# PFC_control_board.net
KiCad netlist of a schematic drawn in Altium Designer
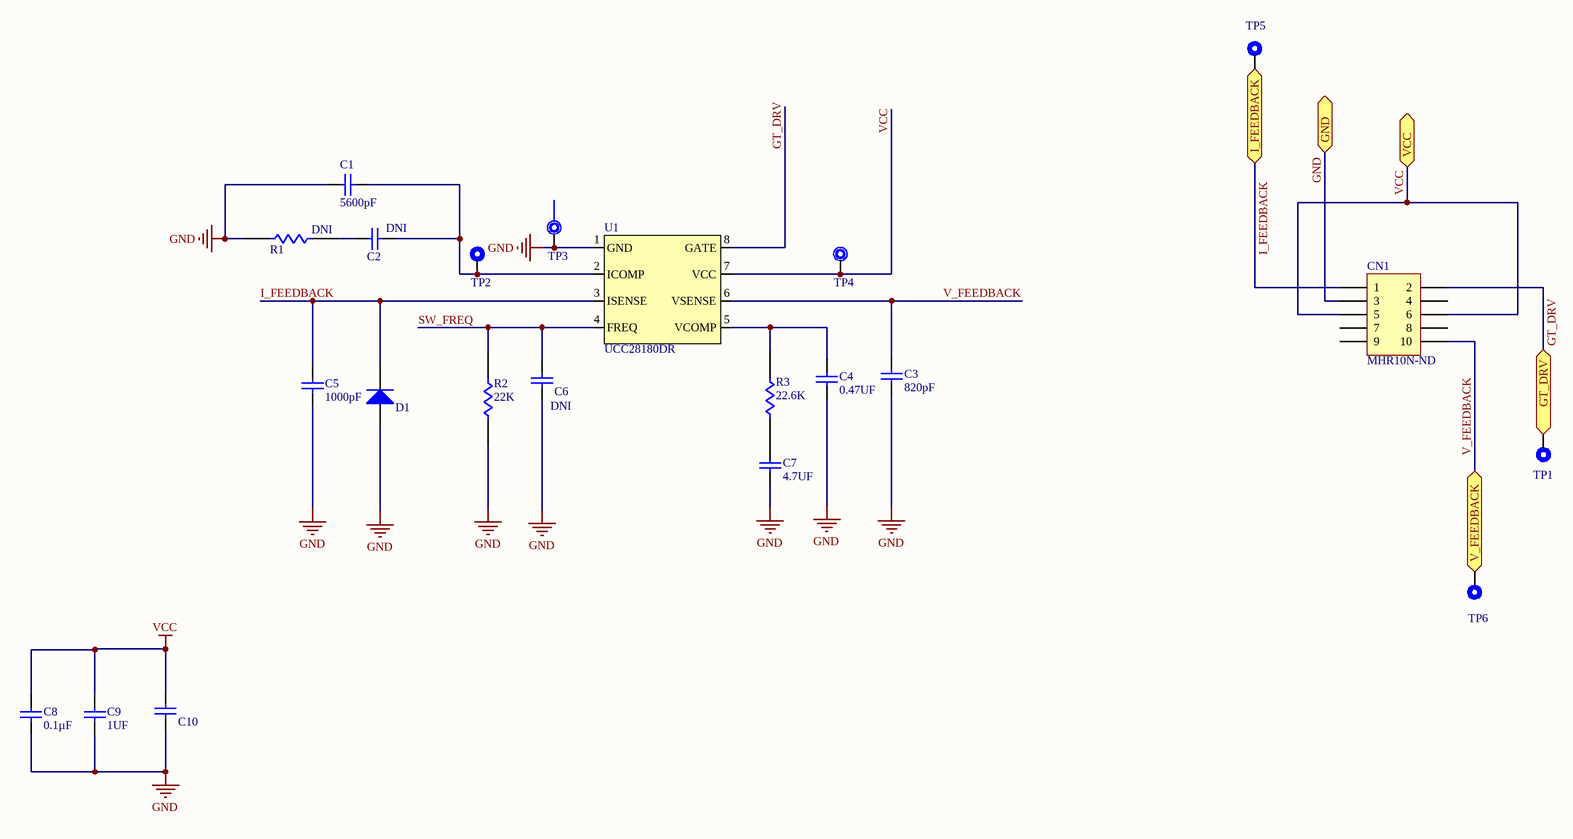
[diagram p0: PFC control board.SchDoc]

(export (version "E")
  (design (tool "Eeschema 10.0.6"))
  (components
    (comp (ref "C1")
      (value "GRM2195C1H562FA01D")
      (footprint "CAP0805_NEW")
      (description "CAP CER 5600PF 50V C0G/NP0 0805")
      (fields
        (field (name "MANUFACTURER") "Murata Electronics North America")
        (field (name "TOLERANCE") "±1%")
        (field (name "CAPACITANCE") "5600pF")
      )
      (libsource (lib "ucc28180-V04") (part "GRM2195C1H562FA01D"))
    )
    (comp (ref "C2")
      (value "C0805_Generic")
      (footprint "CAP0805_NEW")
      (libsource (lib "ucc28180-V04") (part "C0805_Generic"))
    )
    (comp (ref "C3")
      (value "CC0805KRX7R9BB821")
      (footprint "CAP0805_NEW")
      (description "CAP CER 820PF 50V X7R 0805")
      (fields
        (field (name "MANUFACTURER") "Yageo")
        (field (name "TOLERANCE") "±10%")
        (field (name "CAPACITANCE") "820pF")
      )
      (libsource (lib "ucc28180-V04") (part "CC0805KRX7R9BB821"))
    )
    (comp (ref "C4")
      (value "C0805C474J5RACTU")
      (footprint "CAP0805_NEW")
      (description "CAP CER 0.47UF 50V X7R 0805")
      (fields
        (field (name "MANUFACTURER") "KEMET")
        (field (name "TOLERANCE") "±5%")
        (field (name "CAPACITANCE") "0.47UF")
      )
      (libsource (lib "ucc28180-V04") (part "C0805C474J5RACTU"))
    )
    (comp (ref "C5")
      (value "C0805C102J5GACTU")
      (footprint "CAP0805_NEW")
      (description "CAP CER 1000PF 50V C0G/NP0 0805")
      (fields
        (field (name "MANUFACTURER") "KEMET")
        (field (name "TOLERANCE") "±5%")
        (field (name "CAPACITANCE") "1000pF")
      )
      (libsource (lib "ucc28180-V04") (part "C0805C102J5GACTU"))
    )
    (comp (ref "C6")
      (value "C0805_Generic")
      (footprint "CAP0805_NEW")
      (libsource (lib "ucc28180-V04") (part "C0805_Generic"))
    )
    (comp (ref "C7")
      (value "GRM21BR61H475KE51L")
      (footprint "CAP0805_NEW")
      (description "CAP CER 4.7UF 50V X5R 0805")
      (fields
        (field (name "MANUFACTURER") "Murata Electronics North America")
        (field (name "TOLERANCE") "±10%")
        (field (name "CAPACITANCE") "4.7UF")
      )
      (libsource (lib "ucc28180-V04") (part "GRM21BR61H475KE51L"))
    )
    (comp (ref "C8")
      (value "C0805C104J5RACAUTO")
      (footprint "CAP0805_NEW")
      (description "CAP CER 0.1UF 50V X7R 0805")
      (fields
        (field (name "MANUFACTURER") "KEMET")
        (field (name "TOLERANCE") "±5%")
        (field (name "CAPACITANCE") "0.1µF")
      )
      (libsource (lib "ucc28180-V04") (part "C0805C104J5RACAUTO"))
    )
    (comp (ref "C9")
      (value "CC0805JKX7R9BB105")
      (footprint "CAP0805_NEW")
      (description "CAP CER 1UF 50V X7R 0805")
      (fields
        (field (name "MANUFACTURER") "Yageo")
        (field (name "TOLERANCE") "±5%")
        (field (name "CAPACITANCE") "1UF")
      )
      (libsource (lib "ucc28180-V04") (part "CC0805JKX7R9BB105"))
    )
    (comp (ref "C10")
      (value "C0805_Generic")
      (footprint "CAP0805_NEW")
      (libsource (lib "ucc28180-V04") (part "C0805_Generic"))
    )
    (comp (ref "CN1")
      (value "MHR10N-ND")
      (footprint "3M15452")
      (description "CONN HEADER 10PS R/A LONG LATCH")
      (fields
        (field (name "MANUFACTURER") "3M")
        (field (name "MANUFACTURER PART NUMBER") "N3793-5302RB")
        (field (name "SUPPLIER PART NUMBER 1") "MHR10N-ND")
      )
      (libsource (lib "ucc28180-V03") (part "MHR10N-ND"))
    )
    (comp (ref "D1")
      (value "MRA4004T3G")
      (footprint "MRA4004T3G")
      (libsource (lib "ucc28180-V04") (part "MRA4004T3G"))
    )
    (comp (ref "R1")
      (value "R0805_Generic")
      (footprint "RES0805_New")
      (libsource (lib "ucc28180-V04") (part "R0805_Generic"))
    )
    (comp (ref "R2")
      (value "22K")
      (footprint "RES0805_New")
      (description "RES SMD 22K OHM 1% 1/8W 0805")
      (fields
        (field (name "MANUFACTURER") "Yageo")
        (field (name "MANUFACTURER PART NUMBER") "RC0805FR-0722KL")
      )
      (libsource (lib "ucc28180-V04") (part "RC0805FR-0722KL"))
    )
    (comp (ref "R3")
      (value "22.6K")
      (footprint "RES0805_New")
      (description "RES SMD 22.6K OHM 1% 1/8W 0805")
      (fields
        (field (name "MANUFACTURER") "Yageo")
        (field (name "MANUFACTURER PART NUMBER") "RC0805FR-0722K6L")
      )
      (libsource (lib "ucc28180-V04") (part "RC0805FR-0722K6L"))
    )
    (comp (ref "TP1")
      (value "5006")
      (footprint "Test Point")
      (description "TEST POINT PC COMPACT .063\"D BLK")
      (libsource (lib "ucc28180-V03") (part "5006"))
    )
    (comp (ref "TP2")
      (value "5006")
      (footprint "Test Point")
      (description "TEST POINT PC COMPACT .063\"D BLK")
      (libsource (lib "ucc28180-V03") (part "5006"))
    )
    (comp (ref "TP3")
      (value "TP-Slot")
      (footprint "TP-Slot")
      (libsource (lib "ucc28180-V03") (part "TP-Slot"))
    )
    (comp (ref "TP4") (value "TP-SM") (footprint "TP-SM") (libsource (lib "ucc28180-V03") (part "TP-SM")))
    (comp (ref "TP5")
      (value "5006")
      (footprint "Test Point")
      (description "TEST POINT PC COMPACT .063\"D BLK")
      (libsource (lib "ucc28180-V03") (part "5006"))
    )
    (comp (ref "TP6")
      (value "5006")
      (footprint "Test Point")
      (description "TEST POINT PC COMPACT .063\"D BLK")
      (libsource (lib "ucc28180-V03") (part "5006"))
    )
    (comp (ref "U1")
      (value "UCC28180DR")
      (footprint "SOP127P600X175-8N")
      (description "IC PFC CTRLR AVERAGE CURR 8SOIC")
      (libsource (lib "ucc28180-V03") (part "UCC28180DR"))
    )
  )
  (nets
    (net (code "1") (name "/GT_DRV") (class "Default")
      (node (ref "CN1") (pin "2") (pinfunction "2_2") (pintype "passive"))
      (node (ref "TP1") (pin "1") (pinfunction "1_1") (pintype "passive"))
      (node (ref "U1") (pin "8") (pinfunction "GATE_8") (pintype "passive"))
    )
    (net (code "2") (name "/I_FEEDBACK") (class "Default")
      (node (ref "C5") (pin "2") (pinfunction "2_2") (pintype "passive"))
      (node (ref "CN1") (pin "1") (pinfunction "1_1") (pintype "passive"))
      (node (ref "D1") (pin "2") (pinfunction "2_2") (pintype "passive"))
      (node (ref "TP5") (pin "1") (pinfunction "1_1") (pintype "passive"))
      (node (ref "U1") (pin "3") (pinfunction "ISENSE_3") (pintype "passive"))
    )
    (net (code "3") (name "/SW_FREQ") (class "Default")
      (node (ref "C6") (pin "2") (pinfunction "2_2") (pintype "passive"))
      (node (ref "R2") (pin "1") (pinfunction "1_1") (pintype "passive"))
      (node (ref "U1") (pin "4") (pinfunction "FREQ_4") (pintype "passive"))
    )
    (net (code "4") (name "/V_FEEDBACK") (class "Default")
      (node (ref "C3") (pin "2") (pinfunction "2_2") (pintype "passive"))
      (node (ref "CN1") (pin "10") (pinfunction "10_10") (pintype "passive"))
      (node (ref "TP6") (pin "1") (pinfunction "1_1") (pintype "passive"))
      (node (ref "U1") (pin "6") (pinfunction "VSENSE_6") (pintype "passive"))
    )
    (net (code "5") (name "GND") (class "Default")
      (node (ref "C1") (pin "1") (pinfunction "1_1") (pintype "passive"))
      (node (ref "C10") (pin "1") (pinfunction "1_1") (pintype "passive"))
      (node (ref "C3") (pin "1") (pinfunction "1_1") (pintype "passive"))
      (node (ref "C4") (pin "1") (pinfunction "1_1") (pintype "passive"))
      (node (ref "C5") (pin "1") (pinfunction "1_1") (pintype "passive"))
      (node (ref "C6") (pin "1") (pinfunction "1_1") (pintype "passive"))
      (node (ref "C7") (pin "1") (pinfunction "1_1") (pintype "passive"))
      (node (ref "C8") (pin "1") (pinfunction "1_1") (pintype "passive"))
      (node (ref "C9") (pin "1") (pinfunction "1_1") (pintype "passive"))
      (node (ref "CN1") (pin "3") (pinfunction "3_3") (pintype "passive"))
      (node (ref "D1") (pin "1") (pinfunction "1_1") (pintype "passive"))
      (node (ref "R1") (pin "2") (pinfunction "2_2") (pintype "passive"))
      (node (ref "R2") (pin "2") (pinfunction "2_2") (pintype "passive"))
      (node (ref "TP3") (pin "1") (pinfunction "1_1") (pintype "passive"))
      (node (ref "U1") (pin "1") (pinfunction "GND_1") (pintype "passive"))
    )
    (net (code "6") (name "Net-(C2-Pad1)") (class "Default")
      (node (ref "C2") (pin "1") (pinfunction "1_1") (pintype "passive"))
      (node (ref "R1") (pin "1") (pinfunction "1_1") (pintype "passive"))
    )
    (net (code "7") (name "Net-(C7-Pad2)") (class "Default")
      (node (ref "C7") (pin "2") (pinfunction "2_2") (pintype "passive"))
      (node (ref "R3") (pin "2") (pinfunction "2_2") (pintype "passive"))
    )
    (net (code "8") (name "Net-(U1-ICOMP)") (class "Default")
      (node (ref "C1") (pin "2") (pinfunction "2_2") (pintype "passive"))
      (node (ref "C2") (pin "2") (pinfunction "2_2") (pintype "passive"))
      (node (ref "TP2") (pin "1") (pinfunction "1_1") (pintype "passive"))
      (node (ref "U1") (pin "2") (pinfunction "ICOMP_2") (pintype "passive"))
    )
    (net (code "9") (name "Net-(U1-VCOMP)") (class "Default")
      (node (ref "C4") (pin "2") (pinfunction "2_2") (pintype "passive"))
      (node (ref "R3") (pin "1") (pinfunction "1_1") (pintype "passive"))
      (node (ref "U1") (pin "5") (pinfunction "VCOMP_5") (pintype "passive"))
    )
    (net (code "10") (name "VCC") (class "Default")
      (node (ref "C10") (pin "2") (pinfunction "2_2") (pintype "passive"))
      (node (ref "C8") (pin "2") (pinfunction "2_2") (pintype "passive"))
      (node (ref "C9") (pin "2") (pinfunction "2_2") (pintype "passive"))
      (node (ref "CN1") (pin "5") (pinfunction "5_5") (pintype "passive"))
      (node (ref "CN1") (pin "6") (pinfunction "6_6") (pintype "passive"))
      (node (ref "TP4") (pin "1") (pinfunction "1_1") (pintype "passive"))
      (node (ref "U1") (pin "7") (pinfunction "VCC_7") (pintype "passive"))
    )
    (net (code "11") (name "unconnected-(CN1-Pad4)") (class "Default")
      (node (ref "CN1") (pin "4") (pinfunction "4_4") (pintype "passive"))
    )
    (net (code "12") (name "unconnected-(CN1-Pad7)") (class "Default")
      (node (ref "CN1") (pin "7") (pinfunction "7_7") (pintype "passive"))
    )
    (net (code "13") (name "unconnected-(CN1-Pad8)") (class "Default")
      (node (ref "CN1") (pin "8") (pinfunction "8_8") (pintype "passive"))
    )
    (net (code "14") (name "unconnected-(CN1-Pad9)") (class "Default")
      (node (ref "CN1") (pin "9") (pinfunction "9_9") (pintype "passive"))
    )
  )
)
